# LEDs.net
KiCad netlist of a schematic drawn in Altium Designer
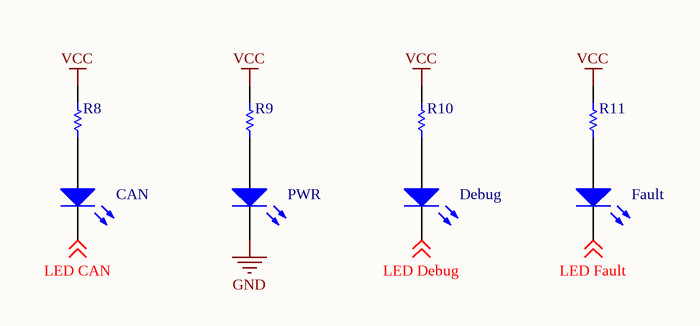
[diagram p0: LEDs.SchDoc]

(export (version "E")
  (design (tool "Eeschema 10.0.6"))
  (components
    (comp (ref "CAN")
      (value "LED")
      (footprint "0805_A")
      (description "Standard 0805 LED")
      (fields (field (name "MANUFACTURER") "Wuerth Elektronik") (field (name "PARTNUMBER") "150080SS75000"))
      (libsource (lib "Husky Robotics Standard Library 2019-2020") (part "LED"))
    )
    (comp (ref "Debug")
      (value "LED")
      (footprint "0805_A")
      (description "Standard 0805 LED")
      (libsource (lib "Husky Robotics Standard Library 2019-2020") (part "LED"))
    )
    (comp (ref "Fault")
      (value "LED")
      (footprint "0805_A")
      (description "Standard 0805 LED")
      (fields (field (name "MANUFACTURER") "Wuerth Elektronik") (field (name "PARTNUMBER") "150080SS75000"))
      (libsource (lib "Husky Robotics Standard Library 2019-2020") (part "LED"))
    )
    (comp (ref "PWR")
      (value "LED")
      (footprint "0805_A")
      (description "Standard 0805 LED")
      (libsource (lib "Husky Robotics Standard Library 2019-2020") (part "LED"))
    )
    (comp (ref "R8")
      (value "Resistor 0805")
      (footprint "RESC0805(2012)_N")
      (description "Generic 0805 Resistor")
      (fields (field (name "TOLERANCE") "5 %") (field (name "POWER") "0.125 W"))
      (libsource (lib "Husky Robotics Standard Library 2019-2020") (part "Resistor 0805"))
    )
    (comp (ref "R9")
      (value "Resistor 0805")
      (footprint "RESC0805(2012)_N")
      (description "Generic 0805 Resistor")
      (fields (field (name "TOLERANCE") "5 %") (field (name "POWER") "0.125 W"))
      (libsource (lib "Husky Robotics Standard Library 2019-2020") (part "Resistor 0805"))
    )
    (comp (ref "R10")
      (value "Resistor 0805")
      (footprint "RESC0805(2012)_N")
      (description "Generic 0805 Resistor")
      (fields (field (name "TOLERANCE") "5 %") (field (name "POWER") "0.125 W"))
      (libsource (lib "Husky Robotics Standard Library 2019-2020") (part "Resistor 0805"))
    )
    (comp (ref "R11")
      (value "Resistor 0805")
      (footprint "RESC0805(2012)_N")
      (description "Generic 0805 Resistor")
      (fields (field (name "TOLERANCE") "5 %") (field (name "POWER") "0.125 W"))
      (libsource (lib "Husky Robotics Standard Library 2019-2020") (part "Resistor 0805"))
    )
  )
  (nets
    (net (code "1") (name "GND") (class "Default")
      (node (ref "PWR") (pin "1") (pinfunction "K_1") (pintype "passive"))
    )
    (net (code "2") (name "LED CAN") (class "Default")
      (node (ref "CAN") (pin "1") (pinfunction "K_1") (pintype "passive"))
    )
    (net (code "3") (name "LED Debug") (class "Default")
      (node (ref "Debug") (pin "1") (pinfunction "K_1") (pintype "passive"))
    )
    (net (code "4") (name "LED Fault") (class "Default")
      (node (ref "Fault") (pin "1") (pinfunction "K_1") (pintype "passive"))
    )
    (net (code "5") (name "Net-(CAN-A)") (class "Default")
      (node (ref "CAN") (pin "2") (pinfunction "A_2") (pintype "passive"))
      (node (ref "R8") (pin "2") (pinfunction "2_2") (pintype "passive"))
    )
    (net (code "6") (name "Net-(Debug-A)") (class "Default")
      (node (ref "Debug") (pin "2") (pinfunction "A_2") (pintype "passive"))
      (node (ref "R10") (pin "2") (pinfunction "2_2") (pintype "passive"))
    )
    (net (code "7") (name "Net-(Fault-A)") (class "Default")
      (node (ref "Fault") (pin "2") (pinfunction "A_2") (pintype "passive"))
      (node (ref "R11") (pin "2") (pinfunction "2_2") (pintype "passive"))
    )
    (net (code "8") (name "Net-(PWR-A)") (class "Default")
      (node (ref "PWR") (pin "2") (pinfunction "A_2") (pintype "passive"))
      (node (ref "R9") (pin "2") (pinfunction "2_2") (pintype "passive"))
    )
    (net (code "9") (name "VCC") (class "Default")
      (node (ref "R10") (pin "1") (pinfunction "1_1") (pintype "passive"))
      (node (ref "R11") (pin "1") (pinfunction "1_1") (pintype "passive"))
      (node (ref "R8") (pin "1") (pinfunction "1_1") (pintype "passive"))
      (node (ref "R9") (pin "1") (pinfunction "1_1") (pintype "passive"))
    )
  )
)
